# BehaviorShield-DB9-USB.net
KiCad netlist of a schematic drawn in EAGLE
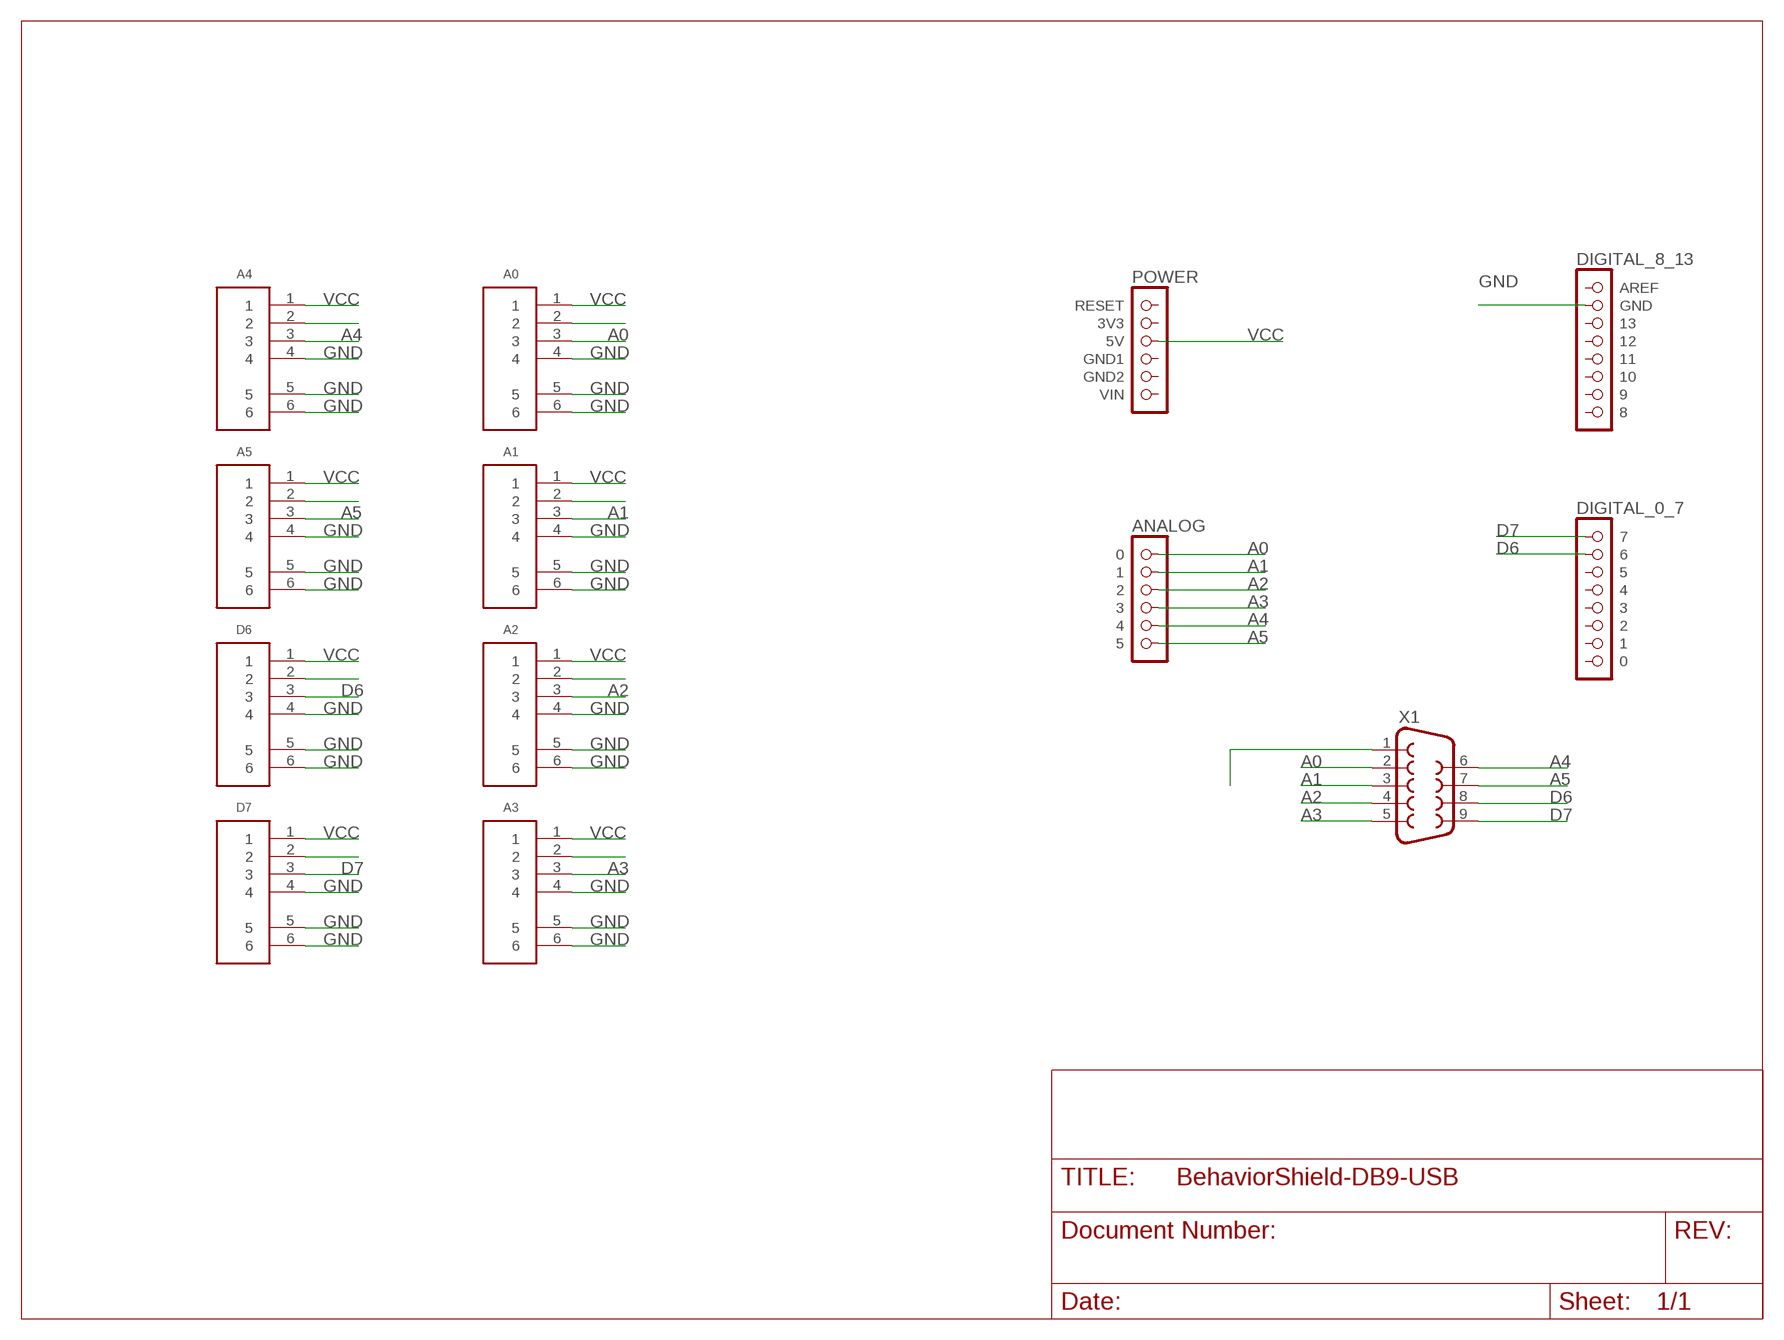
[diagram p0: schematic, sheet 1]

(export (version "E")
  (design (tool "Eeschema 10.0.6"))
  (components
    (comp (ref "A0")
      (value "USB-A-S-X-X-TH")
      (footprint "eagle-import:USB-A-S-X-X-TH")
      (libsource (lib "eagle-import") (part "USB-A-S-X-X-TH"))
    )
    (comp (ref "A1")
      (value "USB-A-S-X-X-TH")
      (footprint "eagle-import:USB-A-S-X-X-TH")
      (libsource (lib "eagle-import") (part "USB-A-S-X-X-TH"))
    )
    (comp (ref "A2")
      (value "USB-A-S-X-X-TH")
      (footprint "eagle-import:USB-A-S-X-X-TH")
      (libsource (lib "eagle-import") (part "USB-A-S-X-X-TH"))
    )
    (comp (ref "A3")
      (value "USB-A-S-X-X-TH")
      (footprint "eagle-import:USB-A-S-X-X-TH")
      (libsource (lib "eagle-import") (part "USB-A-S-X-X-TH"))
    )
    (comp (ref "A4")
      (value "USB-A-S-X-X-TH")
      (footprint "eagle-import:USB-A-S-X-X-TH")
      (libsource (lib "eagle-import") (part "USB-A-S-X-X-TH"))
    )
    (comp (ref "A5")
      (value "USB-A-S-X-X-TH")
      (footprint "eagle-import:USB-A-S-X-X-TH")
      (libsource (lib "eagle-import") (part "USB-A-S-X-X-TH"))
    )
    (comp (ref "D6")
      (value "USB-A-S-X-X-TH")
      (footprint "eagle-import:USB-A-S-X-X-TH")
      (libsource (lib "eagle-import") (part "USB-A-S-X-X-TH"))
    )
    (comp (ref "D7")
      (value "USB-A-S-X-X-TH")
      (footprint "eagle-import:USB-A-S-X-X-TH")
      (libsource (lib "eagle-import") (part "USB-A-S-X-X-TH"))
    )
    (comp (ref "U$1")
      (value "POWER")
      (footprint "eagle-import:1X06")
      (libsource (lib "eagle-import") (part "POWER"))
    )
    (comp (ref "U$2")
      (value "ANALOG")
      (footprint "eagle-import:1X06")
      (libsource (lib "eagle-import") (part "ANALOG"))
    )
    (comp (ref "U$3")
      (value "DIGITAL_0_7")
      (footprint "eagle-import:1X08")
      (libsource (lib "eagle-import") (part "DIGITAL_0_7"))
    )
    (comp (ref "U$4")
      (value "DIGITAL_8_13")
      (footprint "eagle-import:1X08")
      (libsource (lib "eagle-import") (part "DIGITAL_8_13"))
    )
    (comp (ref "X1")
      (value "F09HP")
      (footprint "eagle-import:F09HP")
      (libsource (lib "eagle-import") (part "F09HP"))
    )
  )
  (nets
    (net (code "1") (name "/A0") (class "Default")
      (node (ref "A0") (pin "3") (pinfunction "3_3") (pintype "bidirectional"))
      (node (ref "U$2") (pin "1") (pinfunction "0_1") (pintype "passive"))
      (node (ref "X1") (pin "2") (pinfunction "2_2") (pintype "passive"))
    )
    (net (code "2") (name "/A1") (class "Default")
      (node (ref "A1") (pin "3") (pinfunction "3_3") (pintype "bidirectional"))
      (node (ref "U$2") (pin "2") (pinfunction "1_2") (pintype "passive"))
      (node (ref "X1") (pin "3") (pinfunction "3_3") (pintype "passive"))
    )
    (net (code "3") (name "/A2") (class "Default")
      (node (ref "A2") (pin "3") (pinfunction "3_3") (pintype "bidirectional"))
      (node (ref "U$2") (pin "3") (pinfunction "2_3") (pintype "passive"))
      (node (ref "X1") (pin "4") (pinfunction "4_4") (pintype "passive"))
    )
    (net (code "4") (name "/A3") (class "Default")
      (node (ref "A3") (pin "3") (pinfunction "3_3") (pintype "bidirectional"))
      (node (ref "U$2") (pin "4") (pinfunction "3_4") (pintype "passive"))
      (node (ref "X1") (pin "5") (pinfunction "5_5") (pintype "passive"))
    )
    (net (code "5") (name "/A4") (class "Default")
      (node (ref "A4") (pin "3") (pinfunction "3_3") (pintype "bidirectional"))
      (node (ref "U$2") (pin "5") (pinfunction "4_5") (pintype "passive"))
      (node (ref "X1") (pin "6") (pinfunction "6_6") (pintype "passive"))
    )
    (net (code "6") (name "/A5") (class "Default")
      (node (ref "A5") (pin "3") (pinfunction "3_3") (pintype "bidirectional"))
      (node (ref "U$2") (pin "6") (pinfunction "5_6") (pintype "passive"))
      (node (ref "X1") (pin "7") (pinfunction "7_7") (pintype "passive"))
    )
    (net (code "7") (name "/D6") (class "Default")
      (node (ref "D6") (pin "3") (pinfunction "3_3") (pintype "bidirectional"))
      (node (ref "U$3") (pin "2") (pinfunction "6_2") (pintype "passive"))
      (node (ref "X1") (pin "8") (pinfunction "8_8") (pintype "passive"))
    )
    (net (code "8") (name "/D7") (class "Default")
      (node (ref "D7") (pin "3") (pinfunction "3_3") (pintype "bidirectional"))
      (node (ref "U$3") (pin "1") (pinfunction "7_1") (pintype "passive"))
      (node (ref "X1") (pin "9") (pinfunction "9_9") (pintype "passive"))
    )
    (net (code "9") (name "/GND") (class "Default")
      (node (ref "A0") (pin "4") (pinfunction "4_4") (pintype "bidirectional"))
      (node (ref "A0") (pin "5") (pinfunction "5_5") (pintype "bidirectional"))
      (node (ref "A0") (pin "6") (pinfunction "6_6") (pintype "bidirectional"))
      (node (ref "A1") (pin "4") (pinfunction "4_4") (pintype "bidirectional"))
      (node (ref "A1") (pin "5") (pinfunction "5_5") (pintype "bidirectional"))
      (node (ref "A1") (pin "6") (pinfunction "6_6") (pintype "bidirectional"))
      (node (ref "A2") (pin "4") (pinfunction "4_4") (pintype "bidirectional"))
      (node (ref "A2") (pin "5") (pinfunction "5_5") (pintype "bidirectional"))
      (node (ref "A2") (pin "6") (pinfunction "6_6") (pintype "bidirectional"))
      (node (ref "A3") (pin "4") (pinfunction "4_4") (pintype "bidirectional"))
      (node (ref "A3") (pin "5") (pinfunction "5_5") (pintype "bidirectional"))
      (node (ref "A3") (pin "6") (pinfunction "6_6") (pintype "bidirectional"))
      (node (ref "A4") (pin "4") (pinfunction "4_4") (pintype "bidirectional"))
      (node (ref "A4") (pin "5") (pinfunction "5_5") (pintype "bidirectional"))
      (node (ref "A4") (pin "6") (pinfunction "6_6") (pintype "bidirectional"))
      (node (ref "A5") (pin "4") (pinfunction "4_4") (pintype "bidirectional"))
      (node (ref "A5") (pin "5") (pinfunction "5_5") (pintype "bidirectional"))
      (node (ref "A5") (pin "6") (pinfunction "6_6") (pintype "bidirectional"))
      (node (ref "D6") (pin "4") (pinfunction "4_4") (pintype "bidirectional"))
      (node (ref "D6") (pin "5") (pinfunction "5_5") (pintype "bidirectional"))
      (node (ref "D6") (pin "6") (pinfunction "6_6") (pintype "bidirectional"))
      (node (ref "D7") (pin "4") (pinfunction "4_4") (pintype "bidirectional"))
      (node (ref "D7") (pin "5") (pinfunction "5_5") (pintype "bidirectional"))
      (node (ref "D7") (pin "6") (pinfunction "6_6") (pintype "bidirectional"))
      (node (ref "U$4") (pin "2") (pinfunction "GND_2") (pintype "passive"))
      (node (ref "X1") (pin "1") (pinfunction "1_1") (pintype "passive"))
    )
    (net (code "10") (name "/VCC") (class "Default")
      (node (ref "A0") (pin "1") (pinfunction "1_1") (pintype "bidirectional"))
      (node (ref "A1") (pin "1") (pinfunction "1_1") (pintype "bidirectional"))
      (node (ref "A2") (pin "1") (pinfunction "1_1") (pintype "bidirectional"))
      (node (ref "A3") (pin "1") (pinfunction "1_1") (pintype "bidirectional"))
      (node (ref "A4") (pin "1") (pinfunction "1_1") (pintype "bidirectional"))
      (node (ref "A5") (pin "1") (pinfunction "1_1") (pintype "bidirectional"))
      (node (ref "D6") (pin "1") (pinfunction "1_1") (pintype "bidirectional"))
      (node (ref "D7") (pin "1") (pinfunction "1_1") (pintype "bidirectional"))
      (node (ref "U$1") (pin "3") (pinfunction "5V_3") (pintype "passive"))
    )
    (net (code "11") (name "unconnected-(A0-Pad2)") (class "Default")
      (node (ref "A0") (pin "2") (pinfunction "2_2") (pintype "bidirectional"))
    )
    (net (code "12") (name "unconnected-(A1-Pad2)") (class "Default")
      (node (ref "A1") (pin "2") (pinfunction "2_2") (pintype "bidirectional"))
    )
    (net (code "13") (name "unconnected-(A2-Pad2)") (class "Default")
      (node (ref "A2") (pin "2") (pinfunction "2_2") (pintype "bidirectional"))
    )
    (net (code "14") (name "unconnected-(A3-Pad2)") (class "Default")
      (node (ref "A3") (pin "2") (pinfunction "2_2") (pintype "bidirectional"))
    )
    (net (code "15") (name "unconnected-(A4-Pad2)") (class "Default")
      (node (ref "A4") (pin "2") (pinfunction "2_2") (pintype "bidirectional"))
    )
    (net (code "16") (name "unconnected-(A5-Pad2)") (class "Default")
      (node (ref "A5") (pin "2") (pinfunction "2_2") (pintype "bidirectional"))
    )
    (net (code "17") (name "unconnected-(D6-Pad2)") (class "Default")
      (node (ref "D6") (pin "2") (pinfunction "2_2") (pintype "bidirectional"))
    )
    (net (code "18") (name "unconnected-(D7-Pad2)") (class "Default")
      (node (ref "D7") (pin "2") (pinfunction "2_2") (pintype "bidirectional"))
    )
    (net (code "19") (name "unconnected-(U$1-3V3-Pad2)") (class "Default")
      (node (ref "U$1") (pin "2") (pinfunction "3V3_2") (pintype "passive"))
    )
    (net (code "20") (name "unconnected-(U$1-GND1-Pad4)") (class "Default")
      (node (ref "U$1") (pin "4") (pinfunction "GND1_4") (pintype "passive"))
    )
    (net (code "21") (name "unconnected-(U$1-GND2-Pad5)") (class "Default")
      (node (ref "U$1") (pin "5") (pinfunction "GND2_5") (pintype "passive"))
    )
    (net (code "22") (name "unconnected-(U$1-RESET-Pad1)") (class "Default")
      (node (ref "U$1") (pin "1") (pinfunction "RESET_1") (pintype "passive"))
    )
    (net (code "23") (name "unconnected-(U$1-VIN-Pad6)") (class "Default")
      (node (ref "U$1") (pin "6") (pinfunction "VIN_6") (pintype "passive"))
    )
    (net (code "24") (name "unconnected-(U$3-0-Pad8)") (class "Default")
      (node (ref "U$3") (pin "8") (pinfunction "0_8") (pintype "passive"))
    )
    (net (code "25") (name "unconnected-(U$3-1-Pad7)") (class "Default")
      (node (ref "U$3") (pin "7") (pinfunction "1_7") (pintype "passive"))
    )
    (net (code "26") (name "unconnected-(U$3-2-Pad6)") (class "Default")
      (node (ref "U$3") (pin "6") (pinfunction "2_6") (pintype "passive"))
    )
    (net (code "27") (name "unconnected-(U$3-3-Pad5)") (class "Default")
      (node (ref "U$3") (pin "5") (pinfunction "3_5") (pintype "passive"))
    )
    (net (code "28") (name "unconnected-(U$3-5-Pad3)") (class "Default")
      (node (ref "U$3") (pin "3") (pinfunction "5_3") (pintype "passive"))
    )
    (net (code "29") (name "unconnected-(U$3-Pad4)") (class "Default")
      (node (ref "U$3") (pin "4") (pinfunction "4_4") (pintype "passive"))
    )
    (net (code "30") (name "unconnected-(U$4-9-Pad7)") (class "Default")
      (node (ref "U$4") (pin "7") (pinfunction "9_7") (pintype "passive"))
    )
    (net (code "31") (name "unconnected-(U$4-10-Pad6)") (class "Default")
      (node (ref "U$4") (pin "6") (pinfunction "10_6") (pintype "passive"))
    )
    (net (code "32") (name "unconnected-(U$4-11-Pad5)") (class "Default")
      (node (ref "U$4") (pin "5") (pinfunction "11_5") (pintype "passive"))
    )
    (net (code "33") (name "unconnected-(U$4-12-Pad4)") (class "Default")
      (node (ref "U$4") (pin "4") (pinfunction "12_4") (pintype "passive"))
    )
    (net (code "34") (name "unconnected-(U$4-13-Pad3)") (class "Default")
      (node (ref "U$4") (pin "3") (pinfunction "13_3") (pintype "passive"))
    )
    (net (code "35") (name "unconnected-(U$4-AREF-Pad1)") (class "Default")
      (node (ref "U$4") (pin "1") (pinfunction "AREF_1") (pintype "passive"))
    )
    (net (code "36") (name "unconnected-(U$4-Pad8)") (class "Default")
      (node (ref "U$4") (pin "8") (pinfunction "8_8") (pintype "passive"))
    )
  )
)
